# soil_mite_v1.net
KiCad netlist of a schematic drawn in EAGLE
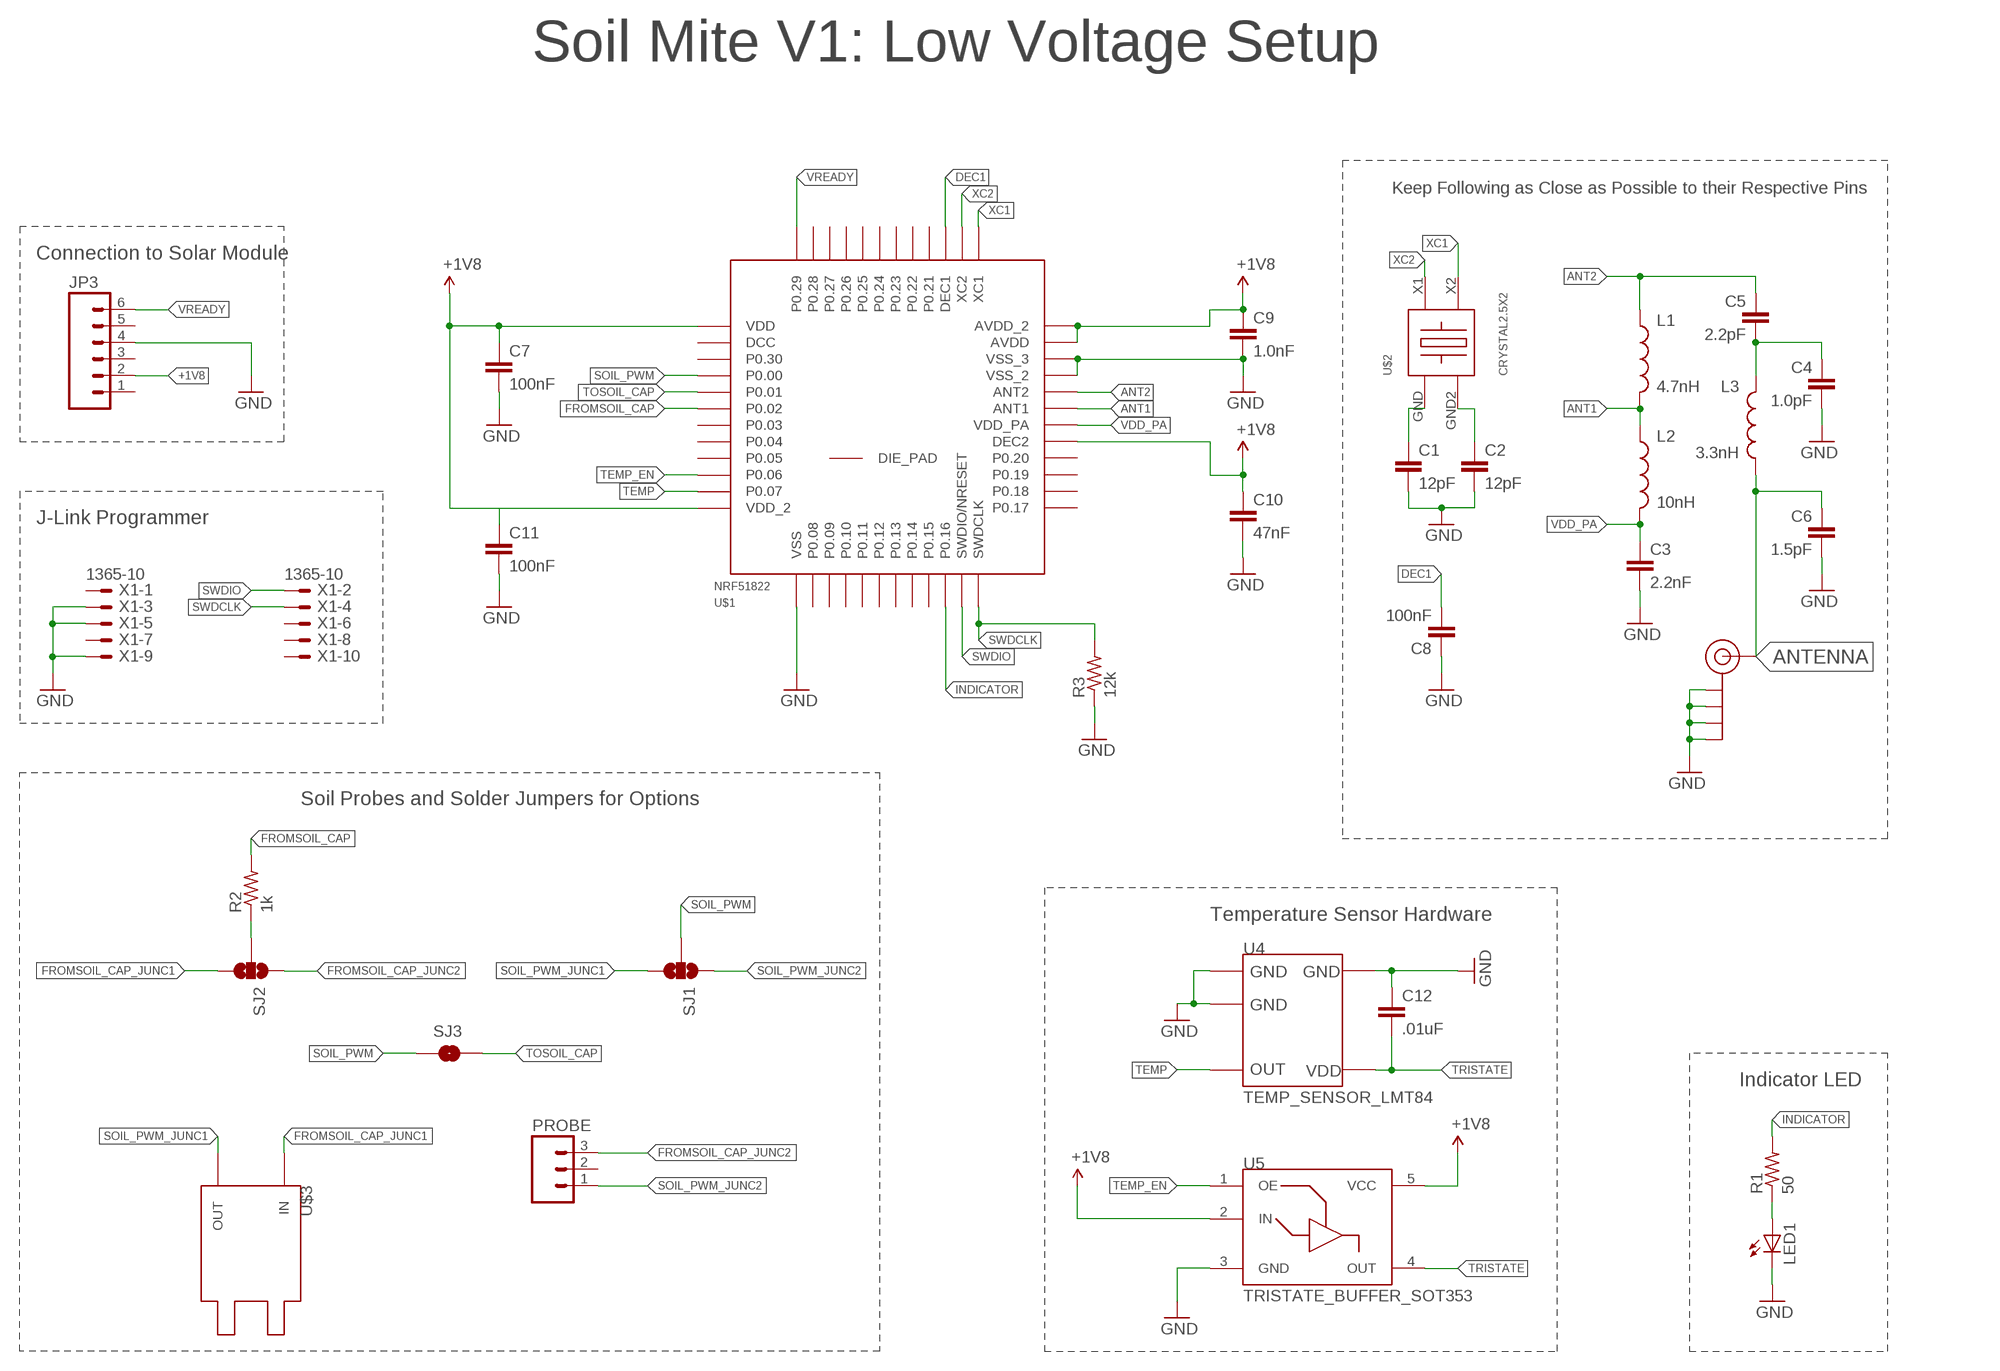
[diagram p0: schematic, sheet 1]

(export (version "E")
  (design (tool "Eeschema 10.0.6"))
  (components
    (comp (ref "C1")
      (value "12pF")
      (footprint "eagle-import:0402-CAP")
      (libsource (lib "eagle-import") (part "CAP0402-CAP"))
    )
    (comp (ref "C2")
      (value "12pF")
      (footprint "eagle-import:0402-CAP")
      (libsource (lib "eagle-import") (part "CAP0402-CAP"))
    )
    (comp (ref "C3")
      (value "2.2nF")
      (footprint "eagle-import:0402-CAP")
      (libsource (lib "eagle-import") (part "CAP0402-CAP"))
    )
    (comp (ref "C4")
      (value "1.0pF")
      (footprint "eagle-import:0402-CAP")
      (libsource (lib "eagle-import") (part "CAP0402-CAP"))
    )
    (comp (ref "C5")
      (value "2.2pF")
      (footprint "eagle-import:0402-CAP")
      (libsource (lib "eagle-import") (part "CAP0402-CAP"))
    )
    (comp (ref "C6")
      (value "1.5pF")
      (footprint "eagle-import:0402-CAP")
      (libsource (lib "eagle-import") (part "CAP0402-CAP"))
    )
    (comp (ref "C7")
      (value "100nF")
      (footprint "eagle-import:0402-CAP")
      (libsource (lib "eagle-import") (part "CAP0402-CAP"))
    )
    (comp (ref "C8")
      (value "100nF")
      (footprint "eagle-import:0402-CAP")
      (libsource (lib "eagle-import") (part "CAP0402-CAP"))
    )
    (comp (ref "C9")
      (value "1.0nF")
      (footprint "eagle-import:0402-CAP")
      (libsource (lib "eagle-import") (part "CAP0402-CAP"))
    )
    (comp (ref "C10")
      (value "47nF")
      (footprint "eagle-import:0402-CAP")
      (libsource (lib "eagle-import") (part "CAP0402-CAP"))
    )
    (comp (ref "C11")
      (value "100nF")
      (footprint "eagle-import:0402-CAP")
      (libsource (lib "eagle-import") (part "CAP0402-CAP"))
    )
    (comp (ref "C12")
      (value ".01uF")
      (footprint "eagle-import:0402-CAP")
      (libsource (lib "eagle-import") (part "CAP0402-CAP"))
    )
    (comp (ref "J$1")
      (value "SMA_EDGE")
      (footprint "eagle-import:SMA-EDGE")
      (libsource (lib "eagle-import") (part "SMA_EDGE"))
    )
    (comp (ref "JP3")
      (value "M06POLAR")
      (footprint "eagle-import:MOLEX-1X6")
      (libsource (lib "eagle-import") (part "M06POLAR"))
    )
    (comp (ref "L1")
      (value "4.7nH")
      (footprint "eagle-import:C0402")
      (libsource (lib "eagle-import") (part "INDUCTOR0402"))
    )
    (comp (ref "L2")
      (value "10nH")
      (footprint "eagle-import:C0402")
      (libsource (lib "eagle-import") (part "INDUCTOR0402"))
    )
    (comp (ref "L3")
      (value "3.3nH")
      (footprint "eagle-import:C0402")
      (libsource (lib "eagle-import") (part "INDUCTOR0402"))
    )
    (comp (ref "LED1")
      (value "JON_LIB_LEDCHIPLED_0603")
      (footprint "eagle-import:JON_LIB_CHIPLED_0603")
      (libsource (lib "eagle-import") (part "JON_LIB_LEDCHIPLED_0603"))
    )
    (comp (ref "PROBE")
      (value "M03PTH")
      (footprint "eagle-import:1X03")
      (libsource (lib "eagle-import") (part "M03PTH"))
    )
    (comp (ref "R1")
      (value "50")
      (footprint "eagle-import:R0603")
      (libsource (lib "eagle-import") (part "R-US_R0603"))
    )
    (comp (ref "R2")
      (value "1k")
      (footprint "eagle-import:R0603")
      (libsource (lib "eagle-import") (part "R-US_R0603"))
    )
    (comp (ref "R3")
      (value "12k")
      (footprint "eagle-import:RCL_R0402")
      (libsource (lib "eagle-import") (part "RCL_R-US_R0402"))
    )
    (comp (ref "SJ1")
      (value "SOLDERJUMPER_2WAYT")
      (footprint "eagle-import:SJ_2")
      (libsource (lib "eagle-import") (part "SOLDERJUMPER_2WAYT"))
    )
    (comp (ref "SJ2")
      (value "SOLDERJUMPER_2WAYT")
      (footprint "eagle-import:SJ_2")
      (libsource (lib "eagle-import") (part "SOLDERJUMPER_2WAYT"))
    )
    (comp (ref "SJ3")
      (value "SOLDERJUMPERNO")
      (footprint "eagle-import:SJ_2S-NO")
      (libsource (lib "eagle-import") (part "SOLDERJUMPERNO"))
    )
    (comp (ref "U$1")
      (value "NRF51822")
      (footprint "eagle-import:QFN48")
      (libsource (lib "eagle-import") (part "NRF51822"))
    )
    (comp (ref "U$2")
      (value "CRYSTAL2.5X2")
      (footprint "eagle-import:2.5X2MM")
      (libsource (lib "eagle-import") (part "CRYSTAL2.5X2"))
    )
    (comp (ref "U$3")
      (value "SOIL_PROBE_TOP_TOPOUT-IN")
      (footprint "eagle-import:PROBE_LAYOUT_1_OUT-IN")
      (libsource (lib "eagle-import") (part "SOIL_PROBE_TOP_TOPOUT-IN"))
    )
    (comp (ref "U4")
      (value "TEMP_SENSOR_LMT84")
      (footprint "eagle-import:SOT353")
      (libsource (lib "eagle-import") (part "TEMP_SENSOR_LMT84"))
    )
    (comp (ref "U5")
      (value "TRISTATE_BUFFER_SOT353")
      (footprint "eagle-import:SOT353")
      (libsource (lib "eagle-import") (part "TRISTATE_BUFFER_SOT353"))
    )
    (comp (ref "X1")
      (value "1365-10")
      (footprint "eagle-import:1365-10")
      (libsource (lib "eagle-import") (part "1365-10"))
    )
  )
  (nets
    (net (code "1") (name "+1V8") (class "Default")
      (node (ref "C10") (pin "1") (pinfunction "1_1") (pintype "passive"))
      (node (ref "C11") (pin "1") (pinfunction "1_1") (pintype "passive"))
      (node (ref "C7") (pin "1") (pinfunction "1_1") (pintype "passive"))
      (node (ref "C9") (pin "1") (pinfunction "1_1") (pintype "passive"))
      (node (ref "JP3") (pin "2") (pinfunction "2_2") (pintype "passive"))
      (node (ref "U$1") (pin "1") (pinfunction "VDD_1") (pintype "bidirectional"))
      (node (ref "U$1") (pin "12") (pinfunction "VDD_2_12") (pintype "bidirectional"))
      (node (ref "U$1") (pin "29") (pinfunction "DEC2_29") (pintype "bidirectional"))
      (node (ref "U$1") (pin "35") (pinfunction "AVDD_35") (pintype "bidirectional"))
      (node (ref "U$1") (pin "36") (pinfunction "AVDD_2_36") (pintype "bidirectional"))
      (node (ref "U5") (pin "2") (pinfunction "IN_2") (pintype "bidirectional"))
      (node (ref "U5") (pin "5") (pinfunction "VCC_5") (pintype "bidirectional"))
    )
    (net (code "2") (name "ANT1") (class "Default")
      (node (ref "L1") (pin "2") (pinfunction "2_2") (pintype "passive"))
      (node (ref "L2") (pin "1") (pinfunction "1_1") (pintype "passive"))
      (node (ref "U$1") (pin "31") (pinfunction "ANT1_31") (pintype "bidirectional"))
    )
    (net (code "3") (name "ANT2") (class "Default")
      (node (ref "C5") (pin "1") (pinfunction "1_1") (pintype "passive"))
      (node (ref "L1") (pin "1") (pinfunction "1_1") (pintype "passive"))
      (node (ref "U$1") (pin "32") (pinfunction "ANT2_32") (pintype "bidirectional"))
    )
    (net (code "4") (name "ANTENNA") (class "Default")
      (node (ref "C6") (pin "1") (pinfunction "1_1") (pintype "passive"))
      (node (ref "J$1") (pin "SIG") (pinfunction "SIGNAL_SIG") (pintype "bidirectional"))
      (node (ref "L3") (pin "2") (pinfunction "2_2") (pintype "passive"))
    )
    (net (code "5") (name "DEC1") (class "Default")
      (node (ref "C8") (pin "2") (pinfunction "2_2") (pintype "passive"))
      (node (ref "U$1") (pin "39") (pinfunction "DEC1_39") (pintype "bidirectional"))
    )
    (net (code "6") (name "FROMSOIL_CAP") (class "Default")
      (node (ref "R2") (pin "1") (pinfunction "1_1") (pintype "passive"))
      (node (ref "R2") (pin "2") (pinfunction "2_2") (pintype "passive"))
      (node (ref "SJ2") (pin "2") (pinfunction "2_2") (pintype "passive"))
      (node (ref "U$1") (pin "6") (pinfunction "P0.02_6") (pintype "bidirectional"))
    )
    (net (code "7") (name "FROMSOIL_CAP_JUNC1") (class "Default")
      (node (ref "SJ2") (pin "3") (pinfunction "3_3") (pintype "passive"))
      (node (ref "U$3") (pin "IN") (pinfunction "IN_IN") (pintype "bidirectional"))
    )
    (net (code "8") (name "FROMSOIL_CAP_JUNC2") (class "Default")
      (node (ref "PROBE") (pin "3") (pinfunction "3_3") (pintype "passive"))
      (node (ref "SJ2") (pin "1") (pinfunction "1_1") (pintype "passive"))
    )
    (net (code "9") (name "GND") (class "Default")
      (node (ref "C1") (pin "2") (pinfunction "2_2") (pintype "passive"))
      (node (ref "C10") (pin "2") (pinfunction "2_2") (pintype "passive"))
      (node (ref "C11") (pin "2") (pinfunction "2_2") (pintype "passive"))
      (node (ref "C12") (pin "1") (pinfunction "1_1") (pintype "passive"))
      (node (ref "C2") (pin "2") (pinfunction "2_2") (pintype "passive"))
      (node (ref "C3") (pin "2") (pinfunction "2_2") (pintype "passive"))
      (node (ref "C4") (pin "2") (pinfunction "2_2") (pintype "passive"))
      (node (ref "C6") (pin "2") (pinfunction "2_2") (pintype "passive"))
      (node (ref "C7") (pin "2") (pinfunction "2_2") (pintype "passive"))
      (node (ref "C8") (pin "1") (pinfunction "1_1") (pintype "passive"))
      (node (ref "C9") (pin "2") (pinfunction "2_2") (pintype "passive"))
      (node (ref "J$1") (pin "GND@0") (pinfunction "GND_GND@0") (pintype "bidirectional"))
      (node (ref "J$1") (pin "GND@1") (pinfunction "GND_GND@1") (pintype "bidirectional"))
      (node (ref "J$1") (pin "GND@2") (pinfunction "GND_GND@2") (pintype "bidirectional"))
      (node (ref "J$1") (pin "GND@3") (pinfunction "GND_GND@3") (pintype "bidirectional"))
      (node (ref "JP3") (pin "4") (pinfunction "4_4") (pintype "passive"))
      (node (ref "LED1") (pin "C") (pinfunction "C_C") (pintype "passive"))
      (node (ref "R3") (pin "1") (pinfunction "1_1") (pintype "passive"))
      (node (ref "U$1") (pin "13") (pinfunction "VSS_13") (pintype "bidirectional"))
      (node (ref "U$1") (pin "33") (pinfunction "VSS_2_33") (pintype "bidirectional"))
      (node (ref "U$1") (pin "34") (pinfunction "VSS_3_34") (pintype "bidirectional"))
      (node (ref "U4") (pin "1") (pinfunction "GND_1") (pintype "bidirectional"))
      (node (ref "U4") (pin "2") (pinfunction "GND_2") (pintype "bidirectional"))
      (node (ref "U4") (pin "5") (pinfunction "GND_5") (pintype "bidirectional"))
      (node (ref "U5") (pin "3") (pinfunction "GND_3") (pintype "bidirectional"))
      (node (ref "X1") (pin "3") (pinfunction "S_3") (pintype "passive"))
      (node (ref "X1") (pin "5") (pinfunction "S_5") (pintype "passive"))
      (node (ref "X1") (pin "9") (pinfunction "S_9") (pintype "passive"))
    )
    (net (code "10") (name "INDICATOR") (class "Default")
      (node (ref "R1") (pin "2") (pinfunction "2_2") (pintype "passive"))
      (node (ref "U$1") (pin "22") (pinfunction "P0.16_22") (pintype "bidirectional"))
    )
    (net (code "11") (name "Net-(C1-Pad1)") (class "Default")
      (node (ref "C1") (pin "1") (pinfunction "1_1") (pintype "passive"))
      (node (ref "U$2") (pin "GND") (pinfunction "GND_GND") (pintype "bidirectional"))
    )
    (net (code "12") (name "Net-(C2-Pad1)") (class "Default")
      (node (ref "C2") (pin "1") (pinfunction "1_1") (pintype "passive"))
      (node (ref "U$2") (pin "GND2") (pinfunction "GND2_GND2") (pintype "bidirectional"))
    )
    (net (code "13") (name "Net-(C4-Pad1)") (class "Default")
      (node (ref "C4") (pin "1") (pinfunction "1_1") (pintype "passive"))
      (node (ref "C5") (pin "2") (pinfunction "2_2") (pintype "passive"))
      (node (ref "L3") (pin "1") (pinfunction "1_1") (pintype "passive"))
    )
    (net (code "14") (name "Net-(LED1-PadA)") (class "Default")
      (node (ref "LED1") (pin "A") (pinfunction "A_A") (pintype "passive"))
      (node (ref "R1") (pin "1") (pinfunction "1_1") (pintype "passive"))
    )
    (net (code "15") (name "SOIL_PWM") (class "Default")
      (node (ref "SJ1") (pin "2") (pinfunction "2_2") (pintype "passive"))
      (node (ref "SJ3") (pin "1") (pinfunction "1_1") (pintype "passive"))
      (node (ref "U$1") (pin "4") (pinfunction "P0.00_4") (pintype "bidirectional"))
    )
    (net (code "16") (name "SOIL_PWM_JUNC1") (class "Default")
      (node (ref "SJ1") (pin "3") (pinfunction "3_3") (pintype "passive"))
      (node (ref "U$3") (pin "OUT") (pinfunction "OUT_OUT") (pintype "bidirectional"))
    )
    (net (code "17") (name "SOIL_PWM_JUNC2") (class "Default")
      (node (ref "PROBE") (pin "1") (pinfunction "1_1") (pintype "passive"))
      (node (ref "SJ1") (pin "1") (pinfunction "1_1") (pintype "passive"))
    )
    (net (code "18") (name "SWDCLK") (class "Default")
      (node (ref "R3") (pin "2") (pinfunction "2_2") (pintype "passive"))
      (node (ref "U$1") (pin "24") (pinfunction "SWDCLK_24") (pintype "bidirectional"))
      (node (ref "X1") (pin "4") (pinfunction "S_4") (pintype "passive"))
    )
    (net (code "19") (name "SWDIO") (class "Default")
      (node (ref "U$1") (pin "23") (pinfunction "SWDIO/NRESET_23") (pintype "bidirectional"))
      (node (ref "X1") (pin "2") (pinfunction "S_2") (pintype "passive"))
    )
    (net (code "20") (name "TEMP") (class "Default")
      (node (ref "U$1") (pin "11") (pinfunction "P0.07_11") (pintype "bidirectional"))
      (node (ref "U4") (pin "3") (pinfunction "OUT_3") (pintype "bidirectional"))
    )
    (net (code "21") (name "TEMP_EN") (class "Default")
      (node (ref "U$1") (pin "10") (pinfunction "P0.06_10") (pintype "bidirectional"))
      (node (ref "U5") (pin "1") (pinfunction "OE_1") (pintype "bidirectional"))
    )
    (net (code "22") (name "TOSOIL_CAP") (class "Default")
      (node (ref "SJ3") (pin "2") (pinfunction "2_2") (pintype "passive"))
      (node (ref "U$1") (pin "5") (pinfunction "P0.01_5") (pintype "bidirectional"))
    )
    (net (code "23") (name "TRISTATE") (class "Default")
      (node (ref "C12") (pin "2") (pinfunction "2_2") (pintype "passive"))
      (node (ref "U4") (pin "4") (pinfunction "VDD_4") (pintype "bidirectional"))
      (node (ref "U5") (pin "4") (pinfunction "OUT_4") (pintype "bidirectional"))
    )
    (net (code "24") (name "VDD_PA") (class "Default")
      (node (ref "C3") (pin "1") (pinfunction "1_1") (pintype "passive"))
      (node (ref "L2") (pin "2") (pinfunction "2_2") (pintype "passive"))
      (node (ref "U$1") (pin "30") (pinfunction "VDD_PA_30") (pintype "bidirectional"))
    )
    (net (code "25") (name "VREADY") (class "Default")
      (node (ref "JP3") (pin "6") (pinfunction "6_6") (pintype "passive"))
      (node (ref "U$1") (pin "48") (pinfunction "P0.29_48") (pintype "bidirectional"))
    )
    (net (code "26") (name "XC1") (class "Default")
      (node (ref "U$1") (pin "37") (pinfunction "XC1_37") (pintype "bidirectional"))
      (node (ref "U$2") (pin "X2") (pinfunction "X2_X2") (pintype "bidirectional"))
    )
    (net (code "27") (name "XC2") (class "Default")
      (node (ref "U$1") (pin "38") (pinfunction "XC2_38") (pintype "bidirectional"))
      (node (ref "U$2") (pin "X1") (pinfunction "X1_X1") (pintype "bidirectional"))
    )
    (net (code "28") (name "unconnected-(JP3-Pad1)") (class "Default")
      (node (ref "JP3") (pin "1") (pinfunction "1_1") (pintype "passive"))
    )
    (net (code "29") (name "unconnected-(JP3-Pad3)") (class "Default")
      (node (ref "JP3") (pin "3") (pinfunction "3_3") (pintype "passive"))
    )
    (net (code "30") (name "unconnected-(JP3-Pad5)") (class "Default")
      (node (ref "JP3") (pin "5") (pinfunction "5_5") (pintype "passive"))
    )
    (net (code "31") (name "unconnected-(PROBE-Pad2)") (class "Default")
      (node (ref "PROBE") (pin "2") (pinfunction "2_2") (pintype "passive"))
    )
    (net (code "32") (name "unconnected-(U$1-DCC-Pad2)") (class "Default")
      (node (ref "U$1") (pin "2") (pinfunction "DCC_2") (pintype "bidirectional"))
    )
    (net (code "33") (name "unconnected-(U$1-DIE_PAD-PadGND)") (class "Default")
      (node (ref "U$1") (pin "GND") (pinfunction "DIE_PAD_GND") (pintype "bidirectional"))
    )
    (net (code "34") (name "unconnected-(U$1-P0.03-Pad7)") (class "Default")
      (node (ref "U$1") (pin "7") (pinfunction "P0.03_7") (pintype "bidirectional"))
    )
    (net (code "35") (name "unconnected-(U$1-P0.04-Pad8)") (class "Default")
      (node (ref "U$1") (pin "8") (pinfunction "P0.04_8") (pintype "bidirectional"))
    )
    (net (code "36") (name "unconnected-(U$1-P0.05-Pad9)") (class "Default")
      (node (ref "U$1") (pin "9") (pinfunction "P0.05_9") (pintype "bidirectional"))
    )
    (net (code "37") (name "unconnected-(U$1-P0.08-Pad14)") (class "Default")
      (node (ref "U$1") (pin "14") (pinfunction "P0.08_14") (pintype "bidirectional"))
    )
    (net (code "38") (name "unconnected-(U$1-P0.09-Pad15)") (class "Default")
      (node (ref "U$1") (pin "15") (pinfunction "P0.09_15") (pintype "bidirectional"))
    )
    (net (code "39") (name "unconnected-(U$1-P0.10-Pad16)") (class "Default")
      (node (ref "U$1") (pin "16") (pinfunction "P0.10_16") (pintype "bidirectional"))
    )
    (net (code "40") (name "unconnected-(U$1-P0.11-Pad17)") (class "Default")
      (node (ref "U$1") (pin "17") (pinfunction "P0.11_17") (pintype "bidirectional"))
    )
    (net (code "41") (name "unconnected-(U$1-P0.12-Pad18)") (class "Default")
      (node (ref "U$1") (pin "18") (pinfunction "P0.12_18") (pintype "bidirectional"))
    )
    (net (code "42") (name "unconnected-(U$1-P0.13-Pad19)") (class "Default")
      (node (ref "U$1") (pin "19") (pinfunction "P0.13_19") (pintype "bidirectional"))
    )
    (net (code "43") (name "unconnected-(U$1-P0.14-Pad20)") (class "Default")
      (node (ref "U$1") (pin "20") (pinfunction "P0.14_20") (pintype "bidirectional"))
    )
    (net (code "44") (name "unconnected-(U$1-P0.15-Pad21)") (class "Default")
      (node (ref "U$1") (pin "21") (pinfunction "P0.15_21") (pintype "bidirectional"))
    )
    (net (code "45") (name "unconnected-(U$1-P0.17-Pad25)") (class "Default")
      (node (ref "U$1") (pin "25") (pinfunction "P0.17_25") (pintype "bidirectional"))
    )
    (net (code "46") (name "unconnected-(U$1-P0.18-Pad26)") (class "Default")
      (node (ref "U$1") (pin "26") (pinfunction "P0.18_26") (pintype "bidirectional"))
    )
    (net (code "47") (name "unconnected-(U$1-P0.19-Pad27)") (class "Default")
      (node (ref "U$1") (pin "27") (pinfunction "P0.19_27") (pintype "bidirectional"))
    )
    (net (code "48") (name "unconnected-(U$1-P0.20-Pad28)") (class "Default")
      (node (ref "U$1") (pin "28") (pinfunction "P0.20_28") (pintype "bidirectional"))
    )
    (net (code "49") (name "unconnected-(U$1-P0.21-Pad40)") (class "Default")
      (node (ref "U$1") (pin "40") (pinfunction "P0.21_40") (pintype "bidirectional"))
    )
    (net (code "50") (name "unconnected-(U$1-P0.22-Pad41)") (class "Default")
      (node (ref "U$1") (pin "41") (pinfunction "P0.22_41") (pintype "bidirectional"))
    )
    (net (code "51") (name "unconnected-(U$1-P0.23-Pad42)") (class "Default")
      (node (ref "U$1") (pin "42") (pinfunction "P0.23_42") (pintype "bidirectional"))
    )
    (net (code "52") (name "unconnected-(U$1-P0.24-Pad43)") (class "Default")
      (node (ref "U$1") (pin "43") (pinfunction "P0.24_43") (pintype "bidirectional"))
    )
    (net (code "53") (name "unconnected-(U$1-P0.25-Pad44)") (class "Default")
      (node (ref "U$1") (pin "44") (pinfunction "P0.25_44") (pintype "bidirectional"))
    )
    (net (code "54") (name "unconnected-(U$1-P0.26-Pad45)") (class "Default")
      (node (ref "U$1") (pin "45") (pinfunction "P0.26_45") (pintype "bidirectional"))
    )
    (net (code "55") (name "unconnected-(U$1-P0.27-Pad46)") (class "Default")
      (node (ref "U$1") (pin "46") (pinfunction "P0.27_46") (pintype "bidirectional"))
    )
    (net (code "56") (name "unconnected-(U$1-P0.28-Pad47)") (class "Default")
      (node (ref "U$1") (pin "47") (pinfunction "P0.28_47") (pintype "bidirectional"))
    )
    (net (code "57") (name "unconnected-(U$1-P0.30-Pad3)") (class "Default")
      (node (ref "U$1") (pin "3") (pinfunction "P0.30_3") (pintype "bidirectional"))
    )
    (net (code "58") (name "unconnected-(X1A-S-Pad1)") (class "Default")
      (node (ref "X1") (pin "1") (pinfunction "S_1") (pintype "passive"))
    )
    (net (code "59") (name "unconnected-(X1B-S-Pad10)") (class "Default")
      (node (ref "X1") (pin "10") (pinfunction "S_10") (pintype "passive"))
    )
    (net (code "60") (name "unconnected-(X1G-S-Pad6)") (class "Default")
      (node (ref "X1") (pin "6") (pinfunction "S_6") (pintype "passive"))
    )
    (net (code "61") (name "unconnected-(X1H-S-Pad7)") (class "Default")
      (node (ref "X1") (pin "7") (pinfunction "S_7") (pintype "passive"))
    )
    (net (code "62") (name "unconnected-(X1I-S-Pad8)") (class "Default")
      (node (ref "X1") (pin "8") (pinfunction "S_8") (pintype "passive"))
    )
  )
)
